# sensor.net
KiCad netlist of a schematic drawn in EAGLE
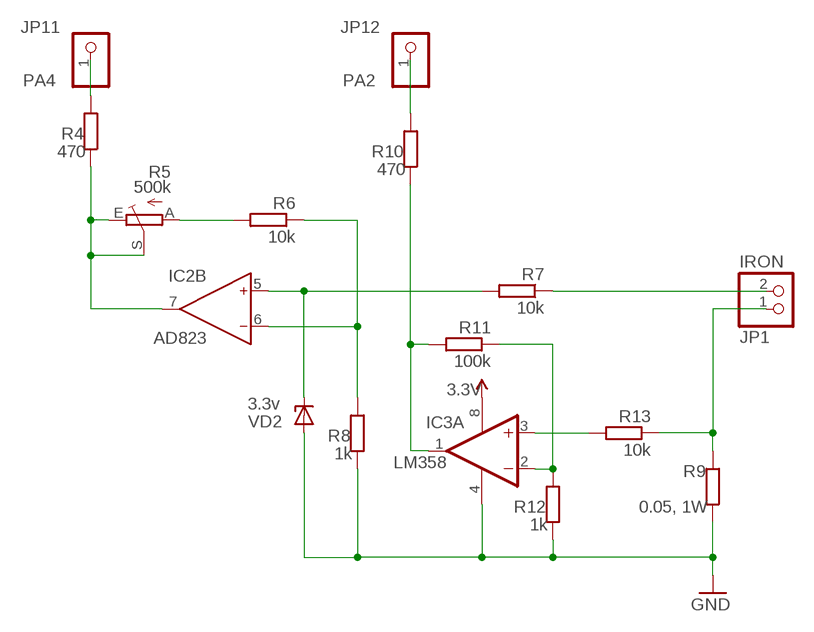
[diagram p0: schematic, sheet 1]

(export (version "E")
  (design (tool "Eeschema 10.0.6"))
  (components
    (comp (ref "IC2")
      (value "AD823")
      (footprint "eagle-import:DIL08")
      (libsource (lib "eagle-import") (part "AD822N"))
    )
    (comp (ref "IC3")
      (value "LM358")
      (footprint "eagle-import:DIL08")
      (libsource (lib "eagle-import") (part "MCP602P"))
    )
    (comp (ref "JP1")
      (value "IRON")
      (footprint "eagle-import:1X02")
      (libsource (lib "eagle-import") (part "PINHD-1X2"))
    )
    (comp (ref "JP11")
      (value "PA4")
      (footprint "eagle-import:1X01")
      (libsource (lib "eagle-import") (part "PINHD-1X1"))
    )
    (comp (ref "JP12")
      (value "PA2")
      (footprint "eagle-import:1X01")
      (libsource (lib "eagle-import") (part "PINHD-1X1"))
    )
    (comp (ref "R4")
      (value "470")
      (footprint "eagle-import:0204_5")
      (libsource (lib "eagle-import") (part "R-EU_0204/5"))
    )
    (comp (ref "R5")
      (value "500k")
      (footprint "eagle-import:B64Y")
      (libsource (lib "eagle-import") (part "TRIM_EU-B64Y"))
    )
    (comp (ref "R6")
      (value "10k")
      (footprint "eagle-import:0204_5")
      (libsource (lib "eagle-import") (part "R-EU_0204/5"))
    )
    (comp (ref "R7")
      (value "10k")
      (footprint "eagle-import:0204_5")
      (libsource (lib "eagle-import") (part "R-EU_0204/5"))
    )
    (comp (ref "R8")
      (value "1k")
      (footprint "eagle-import:0204_5")
      (libsource (lib "eagle-import") (part "R-EU_0204/5"))
    )
    (comp (ref "R9")
      (value "0.05, 1W")
      (footprint "eagle-import:0204_5")
      (libsource (lib "eagle-import") (part "R-EU_0204/5"))
    )
    (comp (ref "R10")
      (value "470")
      (footprint "eagle-import:0204_5")
      (libsource (lib "eagle-import") (part "R-EU_0204/5"))
    )
    (comp (ref "R11")
      (value "100k")
      (footprint "eagle-import:0204_5")
      (libsource (lib "eagle-import") (part "R-EU_0204/5"))
    )
    (comp (ref "R12")
      (value "1k")
      (footprint "eagle-import:0204_5")
      (libsource (lib "eagle-import") (part "R-EU_0204/5"))
    )
    (comp (ref "R13")
      (value "10k")
      (footprint "eagle-import:0204_5")
      (libsource (lib "eagle-import") (part "R-EU_0204/5"))
    )
    (comp (ref "VD2")
      (value "3.3v")
      (footprint "eagle-import:C1702-15")
      (libsource (lib "eagle-import") (part "ZENER-DIODEC1702-15"))
    )
  )
  (nets
    (net (code "1") (name "3.3V") (class "Default")
      (node (ref "IC3") (pin "8") (pinfunction "V+_8") (pintype "power_in"))
    )
    (net (code "2") (name "GND") (class "Default")
      (node (ref "IC3") (pin "4") (pinfunction "V-_4") (pintype "power_in"))
      (node (ref "R12") (pin "1") (pinfunction "1_1") (pintype "passive"))
      (node (ref "R8") (pin "1") (pinfunction "1_1") (pintype "passive"))
      (node (ref "R9") (pin "1") (pinfunction "1_1") (pintype "passive"))
      (node (ref "VD2") (pin "A") (pinfunction "A_A") (pintype "passive"))
    )
    (net (code "3") (name "Net-(IC2B-IN+)") (class "Default")
      (node (ref "IC2") (pin "5") (pinfunction "IN+_5") (pintype "input"))
      (node (ref "R7") (pin "2") (pinfunction "2_2") (pintype "passive"))
      (node (ref "VD2") (pin "C") (pinfunction "C_C") (pintype "passive"))
    )
    (net (code "4") (name "Net-(IC2B-IN-)") (class "Default")
      (node (ref "IC2") (pin "6") (pinfunction "IN-_6") (pintype "input"))
      (node (ref "R6") (pin "1") (pinfunction "1_1") (pintype "passive"))
      (node (ref "R8") (pin "2") (pinfunction "2_2") (pintype "passive"))
    )
    (net (code "5") (name "Net-(IC2B-OUT)") (class "Default")
      (node (ref "IC2") (pin "7") (pinfunction "OUT_7") (pintype "output"))
      (node (ref "R4") (pin "1") (pinfunction "1_1") (pintype "passive"))
      (node (ref "R5") (pin "E") (pinfunction "E_E") (pintype "passive"))
      (node (ref "R5") (pin "S") (pinfunction "S_S") (pintype "passive"))
    )
    (net (code "6") (name "Net-(IC3A-+IN)") (class "Default")
      (node (ref "IC3") (pin "3") (pinfunction "+IN_3") (pintype "input"))
      (node (ref "R13") (pin "2") (pinfunction "2_2") (pintype "passive"))
    )
    (net (code "7") (name "Net-(IC3A--IN)") (class "Default")
      (node (ref "IC3") (pin "2") (pinfunction "-IN_2") (pintype "input"))
      (node (ref "R11") (pin "1") (pinfunction "1_1") (pintype "passive"))
      (node (ref "R12") (pin "2") (pinfunction "2_2") (pintype "passive"))
    )
    (net (code "8") (name "Net-(IC3A-OUT)") (class "Default")
      (node (ref "IC3") (pin "1") (pinfunction "OUT_1") (pintype "output"))
      (node (ref "R10") (pin "1") (pinfunction "1_1") (pintype "passive"))
      (node (ref "R11") (pin "2") (pinfunction "2_2") (pintype "passive"))
    )
    (net (code "9") (name "Net-(JP1-Pad1)") (class "Default")
      (node (ref "JP1") (pin "1") (pinfunction "1_1") (pintype "passive"))
      (node (ref "R13") (pin "1") (pinfunction "1_1") (pintype "passive"))
      (node (ref "R9") (pin "2") (pinfunction "2_2") (pintype "passive"))
    )
    (net (code "10") (name "Net-(JP1-Pad2)") (class "Default")
      (node (ref "JP1") (pin "2") (pinfunction "2_2") (pintype "passive"))
      (node (ref "R7") (pin "1") (pinfunction "1_1") (pintype "passive"))
    )
    (net (code "11") (name "Net-(JP11-Pad1)") (class "Default")
      (node (ref "JP11") (pin "1") (pinfunction "1_1") (pintype "passive"))
      (node (ref "R4") (pin "2") (pinfunction "2_2") (pintype "passive"))
    )
    (net (code "12") (name "Net-(JP12-Pad1)") (class "Default")
      (node (ref "JP12") (pin "1") (pinfunction "1_1") (pintype "passive"))
      (node (ref "R10") (pin "2") (pinfunction "2_2") (pintype "passive"))
    )
    (net (code "13") (name "Net-(R5-PadA)") (class "Default")
      (node (ref "R5") (pin "A") (pinfunction "A_A") (pintype "passive"))
      (node (ref "R6") (pin "2") (pinfunction "2_2") (pintype "passive"))
    )
  )
)
